# EEPROM.net
KiCad netlist of a schematic drawn in Altium Designer
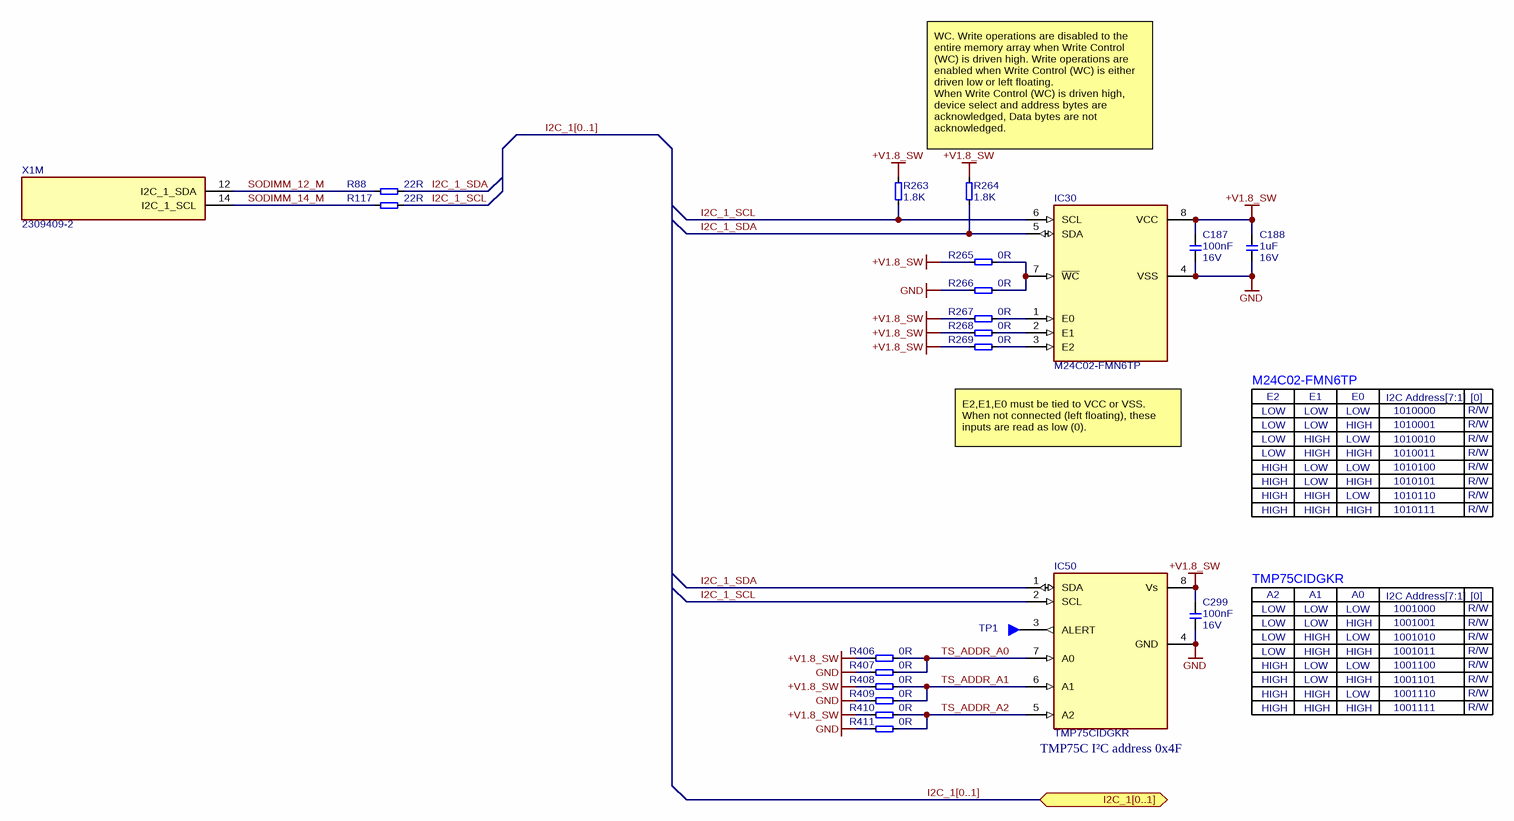
[diagram p0: EEPROM.SchDoc]

(export (version "E")
  (design (tool "Eeschema 10.0.6"))
  (components
    (comp (ref "C187")
      (value "100nF")
      (footprint "CAPC1005X60N")
      (description "Capacitor Ceramic X7R 100nF 16V 10% 0402")
      (fields (field (name "TOLERANCE") "10%") (field (name "RATING") "16V"))
      (libsource (lib "Dahlia Carrier Board") (part "C-X7R-100nF-16V-10%-0402"))
    )
    (comp (ref "C188")
      (value "1uF")
      (footprint "CAPC1005X60N")
      (description "Capacitor Ceramic X5R 1uF 16V 20% 0402")
      (fields (field (name "TOLERANCE") "20%") (field (name "RATING") "16V"))
      (libsource (lib "Dahlia Carrier Board") (part "C-X5R-1uF-16V-20%-0402"))
    )
    (comp (ref "C299")
      (value "100nF")
      (footprint "CAPC1005X60N")
      (description "Capacitor Ceramic X7R 100nF 16V 10% 0402")
      (fields (field (name "TOLERANCE") "10%") (field (name "RATING") "16V"))
      (libsource (lib "Dahlia Carrier Board") (part "C-X7R-100nF-16V-10%-0402"))
    )
    (comp (ref "IC30")
      (value "M24C02-FMN6TP")
      (footprint "IC-SOIC-8N")
      (description "EEPROM, Serial I²C bus , SOIC-8, -40C to +85C")
      (libsource (lib "Dahlia Carrier Board") (part "IC-ST-M24C02-FMN6TP"))
    )
    (comp (ref "IC50")
      (value "TMP75CIDGKR")
      (footprint "IC-TSOP65P490X110-8N")
      (description "Temperature Sensor Digital, Local -55°C ~ 125°C 11 b 8-VSSOP")
      (fields (field (name "MANUFACTURER PART NO.") "TMP75CIDGKR"))
      (libsource (lib "Dahlia Carrier Board") (part "IC-TI-TMP75CIDGKR"))
    )
    (comp (ref "R88")
      (value "22R")
      (footprint "RESC1005X40N")
      (description "Resistor 22 ohm 63mW 5% 0402")
      (fields (field (name "TOLERANCE") "5%"))
      (libsource (lib "Dahlia Carrier Board") (part "R-22R-63mW-5%-0402"))
    )
    (comp (ref "R117")
      (value "22R")
      (footprint "RESC1005X40N")
      (description "Resistor 22 ohm 63mW 5% 0402")
      (fields (field (name "TOLERANCE") "5%"))
      (libsource (lib "Dahlia Carrier Board") (part "R-22R-63mW-5%-0402"))
    )
    (comp (ref "R263")
      (value "1.8K")
      (footprint "RESC1005X40N")
      (description "Resistor 1.8 Kohm 63mW 5% 0402")
      (fields (field (name "TOLERANCE") "5%"))
      (libsource (lib "Dahlia Carrier Board") (part "R-1.8K-63mW-5%-0402"))
    )
    (comp (ref "R264")
      (value "1.8K")
      (footprint "RESC1005X40N")
      (description "Resistor 1.8 Kohm 63mW 5% 0402")
      (fields (field (name "TOLERANCE") "5%"))
      (libsource (lib "Dahlia Carrier Board") (part "R-1.8K-63mW-5%-0402"))
    )
    (comp (ref "R265")
      (value "0R")
      (footprint "T_RESC0603X30N")
      (description "Resistor 0 ohm 63mW 1% 0603")
      (fields (field (name "TOLERANCE") "1%"))
      (libsource (lib "Dahlia Carrier Board") (part "R-0R-63mW-1%-0603"))
    )
    (comp (ref "R266")
      (value "0R")
      (footprint "T_RESC0603X30N")
      (description "Resistor 0 ohm 63mW 1% 0603")
      (fields (field (name "TOLERANCE") "1%"))
      (libsource (lib "Dahlia Carrier Board") (part "R-0R-63mW-1%-0603"))
    )
    (comp (ref "R267")
      (value "0R")
      (footprint "T_RESC0603X30N")
      (description "Resistor 0 ohm 63mW 1% 0603")
      (fields (field (name "TOLERANCE") "1%"))
      (libsource (lib "Dahlia Carrier Board") (part "R-0R-63mW-1%-0603"))
    )
    (comp (ref "R268")
      (value "0R")
      (footprint "T_RESC0603X30N")
      (description "Resistor 0 ohm 63mW 1% 0603")
      (fields (field (name "TOLERANCE") "1%"))
      (libsource (lib "Dahlia Carrier Board") (part "R-0R-63mW-1%-0603"))
    )
    (comp (ref "R269")
      (value "0R")
      (footprint "T_RESC0603X30N")
      (description "Resistor 0 ohm 63mW 1% 0603")
      (fields (field (name "TOLERANCE") "1%"))
      (libsource (lib "Dahlia Carrier Board") (part "R-0R-63mW-1%-0603"))
    )
    (comp (ref "R406")
      (value "0R")
      (footprint "T_RESC0603X30N")
      (description "Resistor 0 ohm 63mW 1% 0603")
      (fields (field (name "TOLERANCE") "1%"))
      (libsource (lib "Dahlia Carrier Board") (part "R-0R-63mW-1%-0603"))
    )
    (comp (ref "R407")
      (value "0R")
      (footprint "T_RESC0603X30N")
      (description "Resistor 0 ohm 63mW 1% 0603")
      (fields (field (name "TOLERANCE") "1%"))
      (libsource (lib "Dahlia Carrier Board") (part "R-0R-63mW-1%-0603"))
    )
    (comp (ref "R408")
      (value "0R")
      (footprint "T_RESC0603X30N")
      (description "Resistor 0 ohm 63mW 1% 0603")
      (fields (field (name "TOLERANCE") "1%"))
      (libsource (lib "Dahlia Carrier Board") (part "R-0R-63mW-1%-0603"))
    )
    (comp (ref "R409")
      (value "0R")
      (footprint "T_RESC0603X30N")
      (description "Resistor 0 ohm 63mW 1% 0603")
      (fields (field (name "TOLERANCE") "1%"))
      (libsource (lib "Dahlia Carrier Board") (part "R-0R-63mW-1%-0603"))
    )
    (comp (ref "R410")
      (value "0R")
      (footprint "T_RESC0603X30N")
      (description "Resistor 0 ohm 63mW 1% 0603")
      (fields (field (name "TOLERANCE") "1%"))
      (libsource (lib "Dahlia Carrier Board") (part "R-0R-63mW-1%-0603"))
    )
    (comp (ref "R411")
      (value "0R")
      (footprint "T_RESC0603X30N")
      (description "Resistor 0 ohm 63mW 1% 0603")
      (fields (field (name "TOLERANCE") "1%"))
      (libsource (lib "Dahlia Carrier Board") (part "R-0R-63mW-1%-0603"))
    )
    (comp (ref "TP1")
      (value "Testpin-SMD")
      (footprint "T_TP-SMD")
      (description "Testpin SMD")
      (libsource (lib "Verdin Development Board") (part "Testpin-SMD"))
    )
    (comp (ref "X1")
      (value "2309409-2")
      (footprint "CON-TE-2309409-2-SOLDERABLE-STANDOFFS")
      (description "DDR4 SODIMM Socket, 260 pins, 5.2mm(H), 0.5mm Pitch")
      (libsource (lib "Dahlia Carrier Board") (part "CON-TE-2309409-2"))
    )
  )
  (nets
    (net (code "3") (name "+V1.8_SW") (class "Default")
      (node (ref "C187") (pin "2") (pinfunction "2_2") (pintype "passive"))
      (node (ref "C188") (pin "2") (pinfunction "2_2") (pintype "passive"))
      (node (ref "C299") (pin "2") (pinfunction "2_2") (pintype "passive"))
      (node (ref "IC30") (pin "8") (pinfunction "VCC_8") (pintype "power_in"))
      (node (ref "IC50") (pin "8") (pinfunction "Vs_8") (pintype "power_in"))
      (node (ref "R263") (pin "1") (pinfunction "1_1") (pintype "passive"))
      (node (ref "R264") (pin "1") (pinfunction "1_1") (pintype "passive"))
      (node (ref "R265") (pin "1") (pinfunction "1_1") (pintype "passive"))
      (node (ref "R267") (pin "1") (pinfunction "1_1") (pintype "passive"))
      (node (ref "R268") (pin "1") (pinfunction "1_1") (pintype "passive"))
      (node (ref "R269") (pin "1") (pinfunction "1_1") (pintype "passive"))
      (node (ref "R406") (pin "1") (pinfunction "1_1") (pintype "passive"))
      (node (ref "R408") (pin "1") (pinfunction "1_1") (pintype "passive"))
      (node (ref "R410") (pin "1") (pinfunction "1_1") (pintype "passive"))
    )
    (net (code "5") (name "/I2C_1_SCL") (class "Default")
      (node (ref "IC30") (pin "6") (pinfunction "SCL_6") (pintype "input"))
      (node (ref "IC50") (pin "2") (pinfunction "SCL_2") (pintype "input"))
      (node (ref "R117") (pin "2") (pinfunction "2_2") (pintype "passive"))
      (node (ref "R263") (pin "2") (pinfunction "2_2") (pintype "passive"))
    )
    (net (code "6") (name "/I2C_1_SDA") (class "Default")
      (node (ref "IC30") (pin "5") (pinfunction "SDA_5") (pintype "bidirectional"))
      (node (ref "IC50") (pin "1") (pinfunction "SDA_1") (pintype "bidirectional"))
      (node (ref "R264") (pin "2") (pinfunction "2_2") (pintype "passive"))
      (node (ref "R88") (pin "2") (pinfunction "2_2") (pintype "passive"))
    )
    (net (code "7") (name "/SODIMM_12_M") (class "Default")
      (node (ref "R88") (pin "1") (pinfunction "1_1") (pintype "passive"))
      (node (ref "X1") (pin "12") (pinfunction "I2C_1_SDA_12") (pintype "passive"))
    )
    (net (code "8") (name "/SODIMM_14_M") (class "Default")
      (node (ref "R117") (pin "1") (pinfunction "1_1") (pintype "passive"))
      (node (ref "X1") (pin "14") (pinfunction "I2C_1_SCL_14") (pintype "passive"))
    )
    (net (code "9") (name "/TS_ADDR_A0") (class "Default")
      (node (ref "IC50") (pin "7") (pinfunction "A0_7") (pintype "input"))
      (node (ref "R406") (pin "2") (pinfunction "2_2") (pintype "passive"))
      (node (ref "R407") (pin "2") (pinfunction "2_2") (pintype "passive"))
    )
    (net (code "10") (name "/TS_ADDR_A1") (class "Default")
      (node (ref "IC50") (pin "6") (pinfunction "A1_6") (pintype "input"))
      (node (ref "R408") (pin "2") (pinfunction "2_2") (pintype "passive"))
      (node (ref "R409") (pin "2") (pinfunction "2_2") (pintype "passive"))
    )
    (net (code "11") (name "/TS_ADDR_A2") (class "Default")
      (node (ref "IC50") (pin "5") (pinfunction "A2_5") (pintype "input"))
      (node (ref "R410") (pin "2") (pinfunction "2_2") (pintype "passive"))
      (node (ref "R411") (pin "2") (pinfunction "2_2") (pintype "passive"))
    )
    (net (code "12") (name "GND") (class "Default")
      (node (ref "C187") (pin "1") (pinfunction "1_1") (pintype "passive"))
      (node (ref "C188") (pin "1") (pinfunction "1_1") (pintype "passive"))
      (node (ref "C299") (pin "1") (pinfunction "1_1") (pintype "passive"))
      (node (ref "IC30") (pin "4") (pinfunction "VSS_4") (pintype "power_in"))
      (node (ref "IC50") (pin "4") (pinfunction "GND_4") (pintype "power_in"))
      (node (ref "R266") (pin "1") (pinfunction "1_1") (pintype "passive"))
      (node (ref "R407") (pin "1") (pinfunction "1_1") (pintype "passive"))
      (node (ref "R409") (pin "1") (pinfunction "1_1") (pintype "passive"))
      (node (ref "R411") (pin "1") (pinfunction "1_1") (pintype "passive"))
    )
    (net (code "13") (name "Net-(IC30-E0)") (class "Default")
      (node (ref "IC30") (pin "1") (pinfunction "E0_1") (pintype "input"))
      (node (ref "R267") (pin "2") (pinfunction "2_2") (pintype "passive"))
    )
    (net (code "14") (name "Net-(IC30-E1)") (class "Default")
      (node (ref "IC30") (pin "2") (pinfunction "E1_2") (pintype "input"))
      (node (ref "R268") (pin "2") (pinfunction "2_2") (pintype "passive"))
    )
    (net (code "15") (name "Net-(IC30-E2)") (class "Default")
      (node (ref "IC30") (pin "3") (pinfunction "E2_3") (pintype "input"))
      (node (ref "R269") (pin "2") (pinfunction "2_2") (pintype "passive"))
    )
    (net (code "16") (name "Net-(IC30-~{WC})") (class "Default")
      (node (ref "IC30") (pin "7") (pinfunction "~{WC}_7") (pintype "input"))
      (node (ref "R265") (pin "2") (pinfunction "2_2") (pintype "passive"))
      (node (ref "R266") (pin "2") (pinfunction "2_2") (pintype "passive"))
    )
    (net (code "17") (name "Net-(IC50-ALERT)") (class "Default")
      (node (ref "IC50") (pin "3") (pinfunction "ALERT_3") (pintype "output"))
      (node (ref "TP1") (pin "1") (pinfunction "1_1") (pintype "passive"))
    )
  )
)
